# Joy2PS2_rev2_3.net
KiCad netlist of a schematic drawn in EAGLE
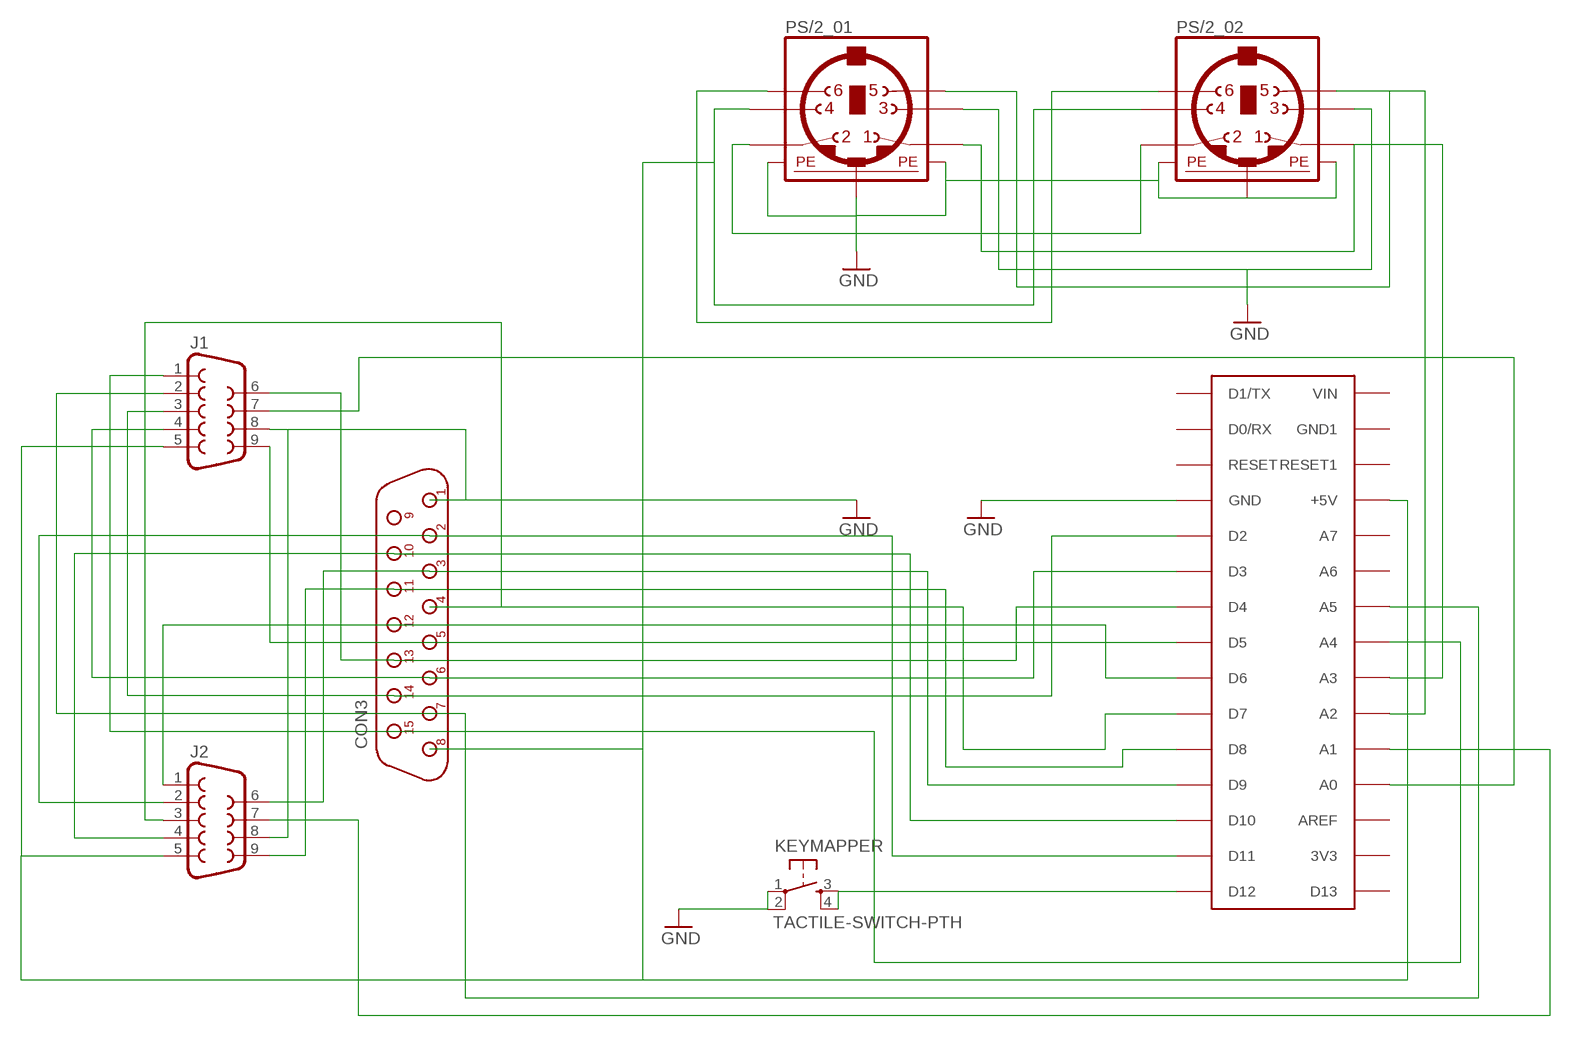
[diagram p0: schematic, sheet 1]

(export (version "E")
  (design (tool "Eeschema 10.0.6"))
  (components
    (comp (ref "ARDUINONANO")
      (value "ARDUINONANO")
      (footprint "eagle-import:PDIP-32")
      (libsource (lib "eagle-import") (part "ARDUINONANO"))
    )
    (comp (ref "CON3")
      (value "DB15M/90")
      (footprint "eagle-import:D-15M_90")
      (libsource (lib "eagle-import") (part "DB15M/90"))
    )
    (comp (ref "J1")
      (value "DB9MALE")
      (footprint "eagle-import:DB9_MALE")
      (libsource (lib "eagle-import") (part "DB9MALE"))
    )
    (comp (ref "J2")
      (value "DB9MALE")
      (footprint "eagle-import:DB9_MALE")
      (libsource (lib "eagle-import") (part "DB9MALE"))
    )
    (comp (ref "KEYMAPPER")
      (value "TACTILE-SWITCH-PTH")
      (footprint "eagle-import:TAC-SWITCH-PTH")
      (libsource (lib "eagle-import") (part "TACTILE-SWITCH-PTH"))
    )
    (comp (ref "PS/2_01")
      (value "MINI_DIN_6")
      (footprint "eagle-import:M_DIN6")
      (libsource (lib "eagle-import") (part "MINI_DIN_6"))
    )
    (comp (ref "PS/2_02")
      (value "MINI_DIN_6")
      (footprint "eagle-import:M_DIN6")
      (libsource (lib "eagle-import") (part "MINI_DIN_6"))
    )
  )
  (nets
    (net (code "1") (name "GND") (class "Default")
      (node (ref "ARDUINONANO") (pin "GND") (pinfunction "GND_GND") (pintype "bidirectional"))
      (node (ref "CON3") (pin "1") (pinfunction "1_1") (pintype "passive"))
      (node (ref "J1") (pin "8") (pinfunction "8_8") (pintype "passive"))
      (node (ref "J2") (pin "8") (pinfunction "8_8") (pintype "passive"))
      (node (ref "KEYMAPPER") (pin "1") (pinfunction "1_1") (pintype "passive"))
      (node (ref "KEYMAPPER") (pin "2") (pinfunction "2_2") (pintype "passive"))
      (node (ref "PS/2_01") (pin "3") (pinfunction "3_3") (pintype "passive"))
      (node (ref "PS/2_01") (pin "SH1") (pinfunction "PE1_SH1") (pintype "power_in"))
      (node (ref "PS/2_01") (pin "SH2") (pinfunction "PE2_SH2") (pintype "power_in"))
      (node (ref "PS/2_01") (pin "SH3") (pinfunction "PE3_SH3") (pintype "power_in"))
      (node (ref "PS/2_02") (pin "3") (pinfunction "3_3") (pintype "passive"))
      (node (ref "PS/2_02") (pin "SH1") (pinfunction "PE1_SH1") (pintype "power_in"))
      (node (ref "PS/2_02") (pin "SH2") (pinfunction "PE2_SH2") (pintype "power_in"))
      (node (ref "PS/2_02") (pin "SH3") (pinfunction "PE3_SH3") (pintype "power_in"))
    )
    (net (code "2") (name "Net-(ARDUINONANO-Pad+5V)") (class "Default")
      (node (ref "ARDUINONANO") (pin "+5V") (pinfunction "+5V_+5V") (pintype "bidirectional"))
      (node (ref "CON3") (pin "8") (pinfunction "8_8") (pintype "passive"))
      (node (ref "J1") (pin "5") (pinfunction "5_5") (pintype "passive"))
      (node (ref "J2") (pin "5") (pinfunction "5_5") (pintype "passive"))
      (node (ref "PS/2_01") (pin "4") (pinfunction "4_4") (pintype "passive"))
      (node (ref "PS/2_02") (pin "4") (pinfunction "4_4") (pintype "passive"))
    )
    (net (code "3") (name "Net-(ARDUINONANO-PadA0)") (class "Default")
      (node (ref "ARDUINONANO") (pin "A0") (pinfunction "A0_A0") (pintype "bidirectional"))
      (node (ref "J1") (pin "7") (pinfunction "7_7") (pintype "passive"))
    )
    (net (code "4") (name "Net-(ARDUINONANO-PadA1)") (class "Default")
      (node (ref "ARDUINONANO") (pin "A1") (pinfunction "A1_A1") (pintype "bidirectional"))
      (node (ref "J2") (pin "7") (pinfunction "7_7") (pintype "passive"))
    )
    (net (code "5") (name "Net-(ARDUINONANO-PadA2)") (class "Default")
      (node (ref "ARDUINONANO") (pin "A2") (pinfunction "A2_A2") (pintype "bidirectional"))
      (node (ref "PS/2_01") (pin "5") (pinfunction "5_5") (pintype "passive"))
      (node (ref "PS/2_02") (pin "5") (pinfunction "5_5") (pintype "passive"))
    )
    (net (code "6") (name "Net-(ARDUINONANO-PadA3)") (class "Default")
      (node (ref "ARDUINONANO") (pin "A3") (pinfunction "A3_A3") (pintype "bidirectional"))
      (node (ref "PS/2_01") (pin "1") (pinfunction "1_1") (pintype "passive"))
      (node (ref "PS/2_02") (pin "1") (pinfunction "1_1") (pintype "passive"))
    )
    (net (code "7") (name "Net-(ARDUINONANO-PadA4)") (class "Default")
      (node (ref "ARDUINONANO") (pin "A4") (pinfunction "A4_A4") (pintype "bidirectional"))
      (node (ref "CON3") (pin "15") (pinfunction "15_15") (pintype "passive"))
      (node (ref "J1") (pin "1") (pinfunction "1_1") (pintype "passive"))
    )
    (net (code "8") (name "Net-(ARDUINONANO-PadA5)") (class "Default")
      (node (ref "ARDUINONANO") (pin "A5") (pinfunction "A5_A5") (pintype "bidirectional"))
      (node (ref "CON3") (pin "7") (pinfunction "7_7") (pintype "passive"))
      (node (ref "J1") (pin "2") (pinfunction "2_2") (pintype "passive"))
    )
    (net (code "9") (name "Net-(ARDUINONANO-PadD2)") (class "Default")
      (node (ref "ARDUINONANO") (pin "D2") (pinfunction "D2_D2") (pintype "bidirectional"))
      (node (ref "CON3") (pin "14") (pinfunction "14_14") (pintype "passive"))
      (node (ref "J1") (pin "3") (pinfunction "3_3") (pintype "passive"))
    )
    (net (code "10") (name "Net-(ARDUINONANO-PadD3)") (class "Default")
      (node (ref "ARDUINONANO") (pin "D3") (pinfunction "D3_D3") (pintype "bidirectional"))
      (node (ref "CON3") (pin "6") (pinfunction "6_6") (pintype "passive"))
      (node (ref "J1") (pin "4") (pinfunction "4_4") (pintype "passive"))
    )
    (net (code "11") (name "Net-(ARDUINONANO-PadD4)") (class "Default")
      (node (ref "ARDUINONANO") (pin "D4") (pinfunction "D4_D4") (pintype "bidirectional"))
      (node (ref "CON3") (pin "13") (pinfunction "13_13") (pintype "passive"))
      (node (ref "J1") (pin "6") (pinfunction "6_6") (pintype "passive"))
    )
    (net (code "12") (name "Net-(ARDUINONANO-PadD5)") (class "Default")
      (node (ref "ARDUINONANO") (pin "D5") (pinfunction "D5_D5") (pintype "bidirectional"))
      (node (ref "CON3") (pin "5") (pinfunction "5_5") (pintype "passive"))
      (node (ref "J1") (pin "9") (pinfunction "9_9") (pintype "passive"))
    )
    (net (code "13") (name "Net-(ARDUINONANO-PadD6)") (class "Default")
      (node (ref "ARDUINONANO") (pin "D6") (pinfunction "D6_D6") (pintype "bidirectional"))
      (node (ref "CON3") (pin "12") (pinfunction "12_12") (pintype "passive"))
      (node (ref "J2") (pin "1") (pinfunction "1_1") (pintype "passive"))
    )
    (net (code "14") (name "Net-(ARDUINONANO-PadD7)") (class "Default")
      (node (ref "ARDUINONANO") (pin "D7") (pinfunction "D7_D7") (pintype "bidirectional"))
      (node (ref "CON3") (pin "4") (pinfunction "4_4") (pintype "passive"))
      (node (ref "J2") (pin "3") (pinfunction "3_3") (pintype "passive"))
    )
    (net (code "15") (name "Net-(ARDUINONANO-PadD8)") (class "Default")
      (node (ref "ARDUINONANO") (pin "D8") (pinfunction "D8_D8") (pintype "bidirectional"))
      (node (ref "CON3") (pin "11") (pinfunction "11_11") (pintype "passive"))
      (node (ref "J2") (pin "9") (pinfunction "9_9") (pintype "passive"))
    )
    (net (code "16") (name "Net-(ARDUINONANO-PadD9)") (class "Default")
      (node (ref "ARDUINONANO") (pin "D9") (pinfunction "D9_D9") (pintype "bidirectional"))
      (node (ref "CON3") (pin "3") (pinfunction "3_3") (pintype "passive"))
      (node (ref "J2") (pin "6") (pinfunction "6_6") (pintype "passive"))
    )
    (net (code "17") (name "Net-(ARDUINONANO-PadD10)") (class "Default")
      (node (ref "ARDUINONANO") (pin "D10") (pinfunction "D10_D10") (pintype "bidirectional"))
      (node (ref "CON3") (pin "10") (pinfunction "10_10") (pintype "passive"))
      (node (ref "J2") (pin "4") (pinfunction "4_4") (pintype "passive"))
    )
    (net (code "18") (name "Net-(ARDUINONANO-PadD11)") (class "Default")
      (node (ref "ARDUINONANO") (pin "D11") (pinfunction "D11_D11") (pintype "bidirectional"))
      (node (ref "CON3") (pin "2") (pinfunction "2_2") (pintype "passive"))
      (node (ref "J2") (pin "2") (pinfunction "2_2") (pintype "passive"))
    )
    (net (code "19") (name "Net-(ARDUINONANO-PadD12)") (class "Default")
      (node (ref "ARDUINONANO") (pin "D12") (pinfunction "D12_D12") (pintype "bidirectional"))
      (node (ref "KEYMAPPER") (pin "3") (pinfunction "3_3") (pintype "passive"))
      (node (ref "KEYMAPPER") (pin "4") (pinfunction "4_4") (pintype "passive"))
    )
    (net (code "20") (name "Net-(PS/2_01-Pad2)") (class "Default")
      (node (ref "PS/2_01") (pin "2") (pinfunction "2_2") (pintype "passive"))
      (node (ref "PS/2_02") (pin "2") (pinfunction "2_2") (pintype "passive"))
    )
    (net (code "21") (name "Net-(PS/2_01-Pad6)") (class "Default")
      (node (ref "PS/2_01") (pin "6") (pinfunction "6_6") (pintype "passive"))
      (node (ref "PS/2_02") (pin "6") (pinfunction "6_6") (pintype "passive"))
    )
    (net (code "22") (name "unconnected-(ARDUINONANO-Pad3V3)") (class "Default")
      (node (ref "ARDUINONANO") (pin "3V3") (pinfunction "3V3_3V3") (pintype "bidirectional"))
    )
    (net (code "23") (name "unconnected-(ARDUINONANO-PadA6)") (class "Default")
      (node (ref "ARDUINONANO") (pin "A6") (pinfunction "A6_A6") (pintype "bidirectional"))
    )
    (net (code "24") (name "unconnected-(ARDUINONANO-PadA7)") (class "Default")
      (node (ref "ARDUINONANO") (pin "A7") (pinfunction "A7_A7") (pintype "bidirectional"))
    )
    (net (code "25") (name "unconnected-(ARDUINONANO-PadAREF)") (class "Default")
      (node (ref "ARDUINONANO") (pin "AREF") (pinfunction "AREF_AREF") (pintype "bidirectional"))
    )
    (net (code "26") (name "unconnected-(ARDUINONANO-PadD0{slash}RX)") (class "Default")
      (node (ref "ARDUINONANO") (pin "D0/RX") (pinfunction "D0/RX_D0/RX") (pintype "bidirectional"))
    )
    (net (code "27") (name "unconnected-(ARDUINONANO-PadD1{slash}TX)") (class "Default")
      (node (ref "ARDUINONANO") (pin "D1/TX") (pinfunction "D1/TX_D1/TX") (pintype "bidirectional"))
    )
    (net (code "28") (name "unconnected-(ARDUINONANO-PadD13)") (class "Default")
      (node (ref "ARDUINONANO") (pin "D13") (pinfunction "D13_D13") (pintype "bidirectional"))
    )
    (net (code "29") (name "unconnected-(ARDUINONANO-PadGND1)") (class "Default")
      (node (ref "ARDUINONANO") (pin "GND1") (pinfunction "GND1_GND1") (pintype "bidirectional"))
    )
    (net (code "30") (name "unconnected-(ARDUINONANO-PadRESET)") (class "Default")
      (node (ref "ARDUINONANO") (pin "RESET") (pinfunction "RESET_RESET") (pintype "bidirectional"))
    )
    (net (code "31") (name "unconnected-(ARDUINONANO-PadRESET1)") (class "Default")
      (node (ref "ARDUINONANO") (pin "RESET1") (pinfunction "RESET1_RESET1") (pintype "bidirectional"))
    )
    (net (code "32") (name "unconnected-(ARDUINONANO-PadVIN)") (class "Default")
      (node (ref "ARDUINONANO") (pin "VIN") (pinfunction "VIN_VIN") (pintype "bidirectional"))
    )
    (net (code "33") (name "unconnected-(CON3-Pad9)") (class "Default")
      (node (ref "CON3") (pin "9") (pinfunction "9_9") (pintype "passive"))
    )
  )
)
